# XLR-F_Breakout.net
KiCad netlist of a schematic drawn in EAGLE
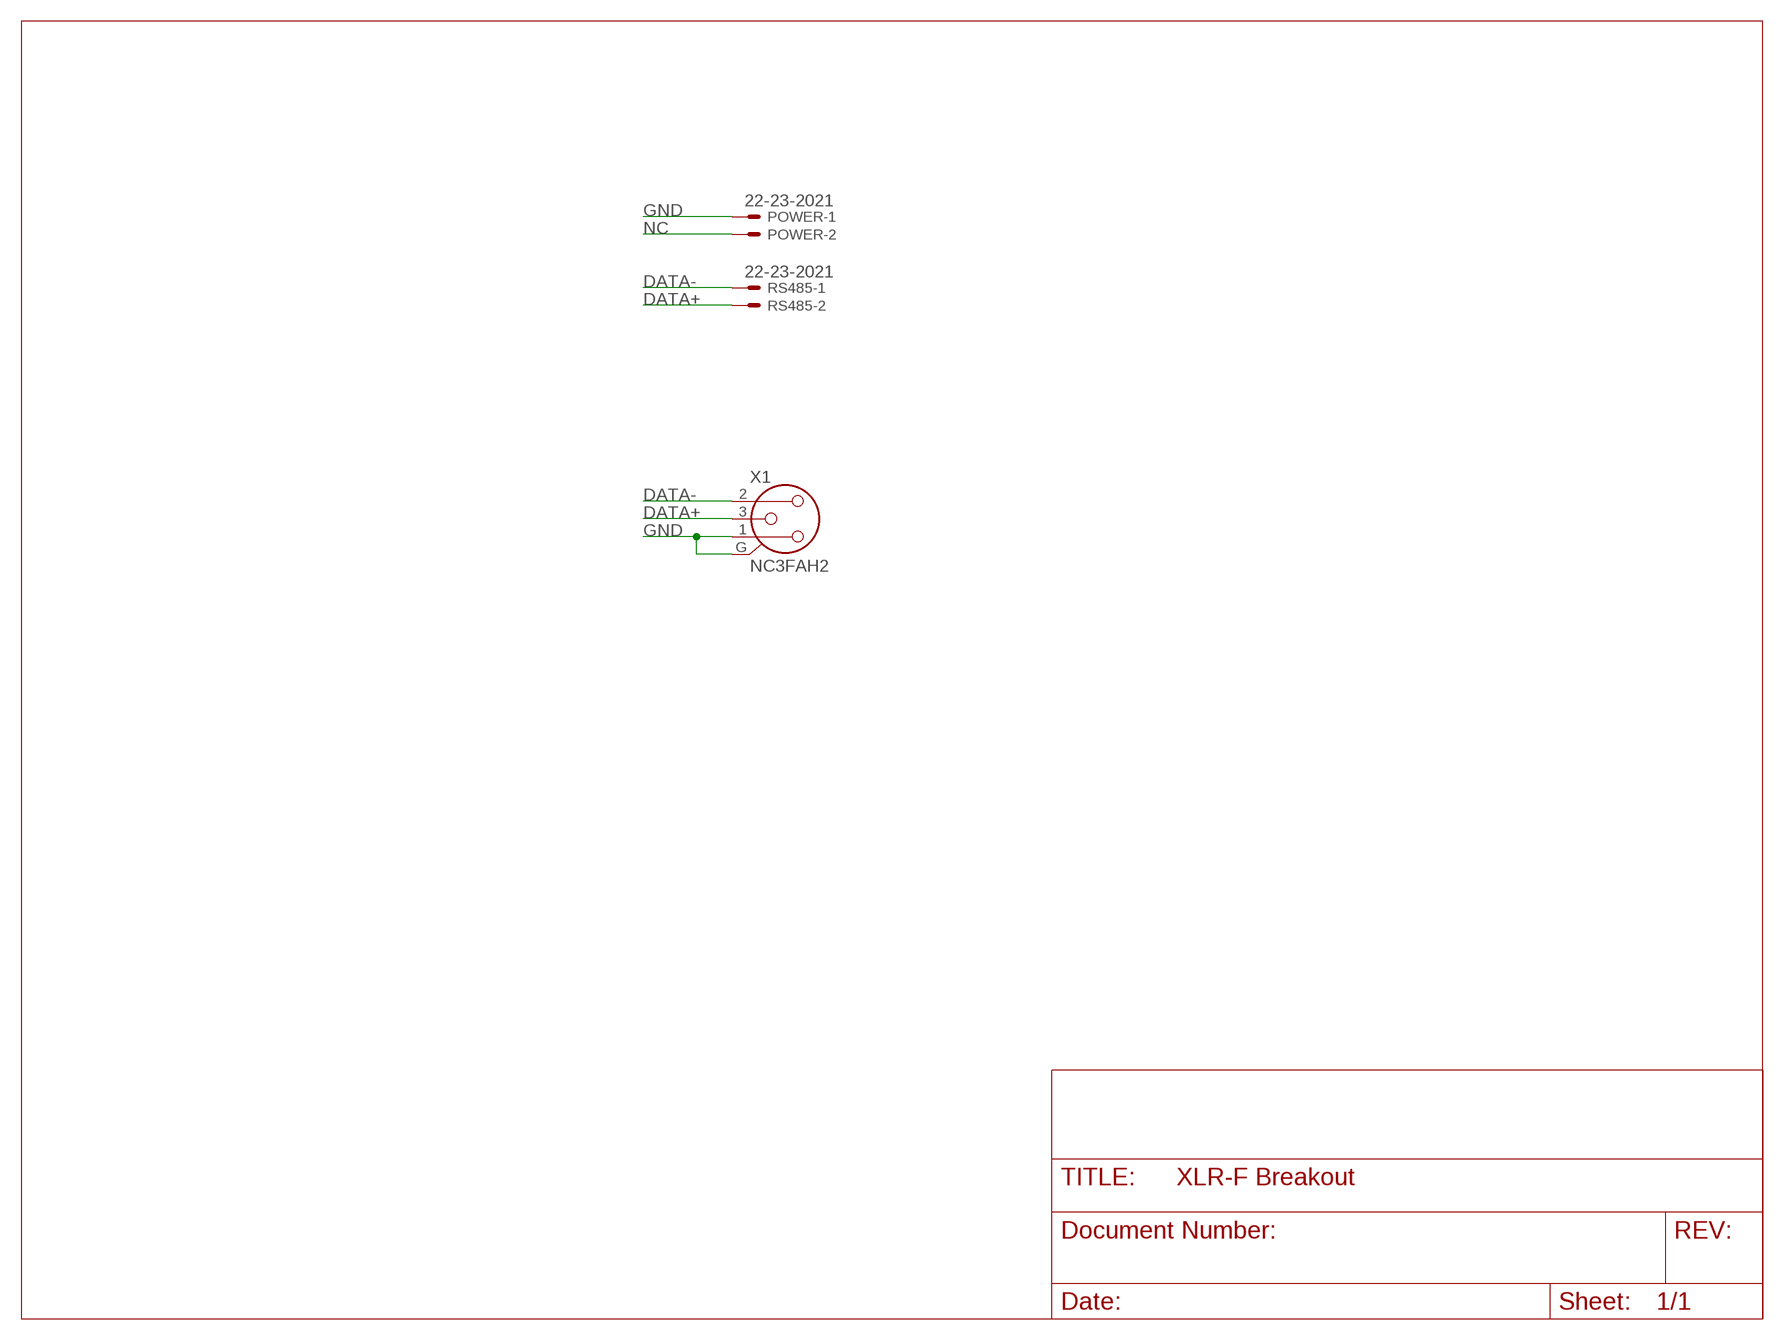
[diagram p0: schematic, sheet 1]

(export (version "E")
  (design (tool "Eeschema 10.0.6"))
  (components
    (comp (ref "POWER")
      (value "22-23-2021")
      (footprint "eagle-import:22-23-2021")
      (fields (field (name "MF") "MOLEX"))
      (libsource (lib "eagle-import") (part "22-23-2021"))
    )
    (comp (ref "RS485")
      (value "22-23-2021")
      (footprint "eagle-import:22-23-2021")
      (fields (field (name "MF") "MOLEX"))
      (libsource (lib "eagle-import") (part "22-23-2021"))
    )
    (comp (ref "X1")
      (value "NC3FAH2")
      (footprint "eagle-import:NC3FAH2")
      (libsource (lib "eagle-import") (part "NC3FAH2"))
    )
  )
  (nets
    (net (code "1") (name "/DATA+") (class "Default")
      (node (ref "RS485") (pin "2") (pinfunction "S_2") (pintype "passive"))
      (node (ref "X1") (pin "3") (pinfunction "3_3") (pintype "passive"))
    )
    (net (code "2") (name "/DATA-") (class "Default")
      (node (ref "RS485") (pin "1") (pinfunction "S_1") (pintype "passive"))
      (node (ref "X1") (pin "2") (pinfunction "1_2") (pintype "passive"))
    )
    (net (code "3") (name "/GND") (class "Default")
      (node (ref "POWER") (pin "1") (pinfunction "S_1") (pintype "passive"))
      (node (ref "X1") (pin "1") (pinfunction "2_1") (pintype "passive"))
      (node (ref "X1") (pin "G") (pinfunction "G_G") (pintype "passive"))
    )
    (net (code "4") (name "/NC") (class "Default")
      (node (ref "POWER") (pin "2") (pinfunction "S_2") (pintype "passive"))
    )
  )
)
